# Buck.net
KiCad netlist of a schematic drawn in Altium Designer
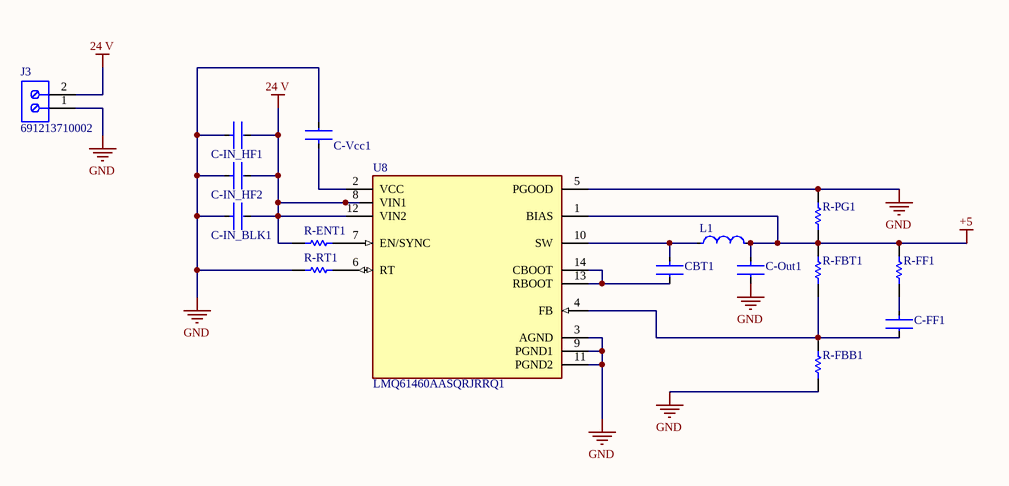
[diagram p0: Buck.SchDoc]

(export (version "E")
  (design (tool "Eeschema 10.0.6"))
  (components
    (comp (ref "C-FF1")
      (value "GRM188R60J106ME47D")
      (footprint "FP-GRM188-0_1-e0_2_0_55-IPC_A")
      (description "Chip Multilayer Ceramic Capacitors for General Purpose, 0603, 10uF, X5R, 15%, 20%, 6.3V")
      (fields (field (name "VOLTAGE") "6.3V") (field (name "TOLERANCE") "20%"))
      (libsource (lib "Altium Content Vault") (part "02cd4be3c70576c341d710602a673aa"))
    )
    (comp (ref "C-IN_BLK1")
      (value "GRM188R60J106ME47D")
      (footprint "FP-GRM188-0_1-e0_2_0_55-IPC_A")
      (description "Chip Multilayer Ceramic Capacitors for General Purpose, 0603, 10uF, X5R, 15%, 20%, 6.3V")
      (fields (field (name "VOLTAGE") "6.3V") (field (name "TOLERANCE") "20%"))
      (libsource (lib "Altium Content Vault") (part "02cd4be3c70576c341d710602a673aa"))
    )
    (comp (ref "C-IN_HF1")
      (value "GRM188R60J106ME47D")
      (footprint "FP-GRM188-0_1-e0_2_0_55-IPC_A")
      (description "Chip Multilayer Ceramic Capacitors for General Purpose, 0603, 10uF, X5R, 15%, 20%, 6.3V")
      (fields (field (name "VOLTAGE") "6.3V") (field (name "TOLERANCE") "20%"))
      (libsource (lib "Altium Content Vault") (part "02cd4be3c70576c341d710602a673aa"))
    )
    (comp (ref "C-IN_HF2")
      (value "GRM188R60J106ME47D")
      (footprint "FP-GRM188-0_1-e0_2_0_55-IPC_A")
      (description "Chip Multilayer Ceramic Capacitors for General Purpose, 0603, 10uF, X5R, 15%, 20%, 6.3V")
      (fields (field (name "VOLTAGE") "6.3V") (field (name "TOLERANCE") "20%"))
      (libsource (lib "Altium Content Vault") (part "02cd4be3c70576c341d710602a673aa"))
    )
    (comp (ref "C-Out1")
      (value "GRM188R60J106ME47D")
      (footprint "FP-GRM188-0_1-e0_2_0_55-IPC_A")
      (description "Chip Multilayer Ceramic Capacitors for General Purpose, 0603, 10uF, X5R, 15%, 20%, 6.3V")
      (fields (field (name "VOLTAGE") "6.3V") (field (name "TOLERANCE") "20%"))
      (libsource (lib "Altium Content Vault") (part "02cd4be3c70576c341d710602a673aa"))
    )
    (comp (ref "C-Vcc1")
      (value "GRM188R60J106ME47D")
      (footprint "FP-GRM188-0_1-e0_2_0_55-IPC_A")
      (description "Chip Multilayer Ceramic Capacitors for General Purpose, 0603, 10uF, X5R, 15%, 20%, 6.3V")
      (fields (field (name "VOLTAGE") "6.3V") (field (name "TOLERANCE") "20%"))
      (libsource (lib "Altium Content Vault") (part "02cd4be3c70576c341d710602a673aa"))
    )
    (comp (ref "CBT1")
      (value "GRM188R60J106ME47D")
      (footprint "FP-GRM188-0_1-e0_2_0_55-IPC_A")
      (description "Chip Multilayer Ceramic Capacitors for General Purpose, 0603, 10uF, X5R, 15%, 20%, 6.3V")
      (fields (field (name "VOLTAGE") "6.3V") (field (name "TOLERANCE") "20%"))
      (libsource (lib "Altium Content Vault") (part "02cd4be3c70576c341d710602a673aa"))
    )
    (comp (ref "J3")
      (value "691213710002")
      (footprint "691213710002")
      (fields (field (name "VOLTAGE") "300V"))
      (libsource (lib "Altium Content Vault") (part "TBL - 1R - 02P - Screw"))
    )
    (comp (ref "L1")
      (value "~")
      (footprint "FP-B82422A-MFG")
      (description "FIXED IND 10UH 180MA 1.6 OHM SMD")
      (fields (field (name "TOLERANCE") "10%"))
      (libsource (lib "Altium Content Vault") (part "725321dda6339637d4d059423bc1c3c"))
    )
    (comp (ref "R-ENT1")
      (value "~")
      (footprint "RESC1609X50X30NL8T20")
      (description "Chip Resistor, 0 Ohm, Jumper, 100 mW, -55 to 155 degC, 0603 (1608 Metric), RoHS, Tape and Reel")
      (fields (field (name "MANUFACTURER") "Vishay Semiconductor"))
      (libsource (lib "Altium Content Vault") (part "RES-2"))
    )
    (comp (ref "R-FBB1")
      (value "~")
      (footprint "RESC1609X50X30NL8T20")
      (description "Chip Resistor, 0 Ohm, Jumper, 100 mW, -55 to 155 degC, 0603 (1608 Metric), RoHS, Tape and Reel")
      (fields (field (name "MANUFACTURER") "Vishay Semiconductor"))
      (libsource (lib "Altium Content Vault") (part "RES-2"))
    )
    (comp (ref "R-FBT1")
      (value "~")
      (footprint "RESC1609X50X30NL8T20")
      (description "Chip Resistor, 0 Ohm, Jumper, 100 mW, -55 to 155 degC, 0603 (1608 Metric), RoHS, Tape and Reel")
      (fields (field (name "MANUFACTURER") "Vishay Semiconductor"))
      (libsource (lib "Altium Content Vault") (part "RES-2"))
    )
    (comp (ref "R-FF1")
      (value "~")
      (footprint "RESC1609X50X30NL8T20")
      (description "Chip Resistor, 0 Ohm, Jumper, 100 mW, -55 to 155 degC, 0603 (1608 Metric), RoHS, Tape and Reel")
      (fields (field (name "MANUFACTURER") "Vishay Semiconductor"))
      (libsource (lib "Altium Content Vault") (part "RES-2"))
    )
    (comp (ref "R-PG1")
      (value "~")
      (footprint "RESC1609X50X30NL8T20")
      (description "Chip Resistor, 0 Ohm, Jumper, 100 mW, -55 to 155 degC, 0603 (1608 Metric), RoHS, Tape and Reel")
      (fields (field (name "MANUFACTURER") "Vishay Semiconductor"))
      (libsource (lib "Altium Content Vault") (part "RES-2"))
    )
    (comp (ref "R-RT1")
      (value "~")
      (footprint "RESC1609X50X30NL8T20")
      (description "Chip Resistor, 0 Ohm, Jumper, 100 mW, -55 to 155 degC, 0603 (1608 Metric), RoHS, Tape and Reel")
      (fields (field (name "MANUFACTURER") "Vishay Semiconductor"))
      (libsource (lib "Altium Content Vault") (part "RES-2"))
    )
    (comp (ref "U8")
      (value "LMQ61460AASQRJRRQ1")
      (footprint "FP-RJR0014A-MFG")
      (description "AUTOMOTIVE 3-V TO 36-V, 6-A LOW")
      (libsource (lib "Altium Content Vault") (part "582341cdab2d02ffbfc5ca31c7a38c5"))
    )
  )
  (nets
    (net (code "1") (name "+5") (class "Default")
      (node (ref "C-Out1") (pin "1") (pinfunction "1_1") (pintype "passive"))
      (node (ref "L1") (pin "2") (pinfunction "2_2") (pintype "passive"))
      (node (ref "R-FBT1") (pin "2") (pinfunction "2_2") (pintype "passive"))
      (node (ref "R-FF1") (pin "2") (pinfunction "2_2") (pintype "passive"))
      (node (ref "R-PG1") (pin "1") (pinfunction "1_1") (pintype "passive"))
      (node (ref "U8") (pin "1") (pinfunction "BIAS_1") (pintype "passive"))
    )
    (net (code "2") (name "24 V") (class "Default")
      (node (ref "C-IN_BLK1") (pin "2") (pinfunction "2_2") (pintype "passive"))
      (node (ref "C-IN_HF1") (pin "2") (pinfunction "2_2") (pintype "passive"))
      (node (ref "C-IN_HF2") (pin "2") (pinfunction "2_2") (pintype "passive"))
      (node (ref "J3") (pin "2") (pinfunction "2_2") (pintype "passive"))
      (node (ref "R-ENT1") (pin "1") (pinfunction "1_1") (pintype "passive"))
      (node (ref "U8") (pin "12") (pinfunction "VIN2_12") (pintype "power_in"))
      (node (ref "U8") (pin "8") (pinfunction "VIN1_8") (pintype "power_in"))
    )
    (net (code "3") (name "GND") (class "Default")
      (node (ref "C-IN_BLK1") (pin "1") (pinfunction "1_1") (pintype "passive"))
      (node (ref "C-IN_HF1") (pin "1") (pinfunction "1_1") (pintype "passive"))
      (node (ref "C-IN_HF2") (pin "1") (pinfunction "1_1") (pintype "passive"))
      (node (ref "C-Out1") (pin "2") (pinfunction "2_2") (pintype "passive"))
      (node (ref "C-Vcc1") (pin "2") (pinfunction "2_2") (pintype "passive"))
      (node (ref "J3") (pin "1") (pinfunction "1_1") (pintype "passive"))
      (node (ref "R-FBB1") (pin "1") (pinfunction "1_1") (pintype "passive"))
      (node (ref "R-PG1") (pin "2") (pinfunction "2_2") (pintype "passive"))
      (node (ref "R-RT1") (pin "1") (pinfunction "1_1") (pintype "passive"))
      (node (ref "U8") (pin "11") (pinfunction "PGND2_11") (pintype "power_in"))
      (node (ref "U8") (pin "3") (pinfunction "AGND_3") (pintype "power_in"))
      (node (ref "U8") (pin "5") (pinfunction "PGOOD_5") (pintype "open_collector"))
      (node (ref "U8") (pin "9") (pinfunction "PGND1_9") (pintype "power_in"))
    )
    (net (code "4") (name "Net-(C-FF1-Pad1)") (class "Default")
      (node (ref "C-FF1") (pin "1") (pinfunction "1_1") (pintype "passive"))
      (node (ref "R-FF1") (pin "1") (pinfunction "1_1") (pintype "passive"))
    )
    (net (code "5") (name "Net-(U8-CBOOT)") (class "Default")
      (node (ref "CBT1") (pin "2") (pinfunction "2_2") (pintype "passive"))
      (node (ref "U8") (pin "13") (pinfunction "RBOOT_13") (pintype "passive"))
      (node (ref "U8") (pin "14") (pinfunction "CBOOT_14") (pintype "passive"))
    )
    (net (code "6") (name "Net-(U8-EN{slash}SYNC)") (class "Default")
      (node (ref "R-ENT1") (pin "2") (pinfunction "2_2") (pintype "passive"))
      (node (ref "U8") (pin "7") (pinfunction "EN/SYNC_7") (pintype "input"))
    )
    (net (code "7") (name "Net-(U8-FB)") (class "Default")
      (node (ref "C-FF1") (pin "2") (pinfunction "2_2") (pintype "passive"))
      (node (ref "R-FBB1") (pin "2") (pinfunction "2_2") (pintype "passive"))
      (node (ref "R-FBT1") (pin "1") (pinfunction "1_1") (pintype "passive"))
      (node (ref "U8") (pin "4") (pinfunction "FB_4") (pintype "input"))
    )
    (net (code "8") (name "Net-(U8-RT)") (class "Default")
      (node (ref "R-RT1") (pin "2") (pinfunction "2_2") (pintype "passive"))
      (node (ref "U8") (pin "6") (pinfunction "RT_6") (pintype "bidirectional"))
    )
    (net (code "9") (name "Net-(U8-SW)") (class "Default")
      (node (ref "CBT1") (pin "1") (pinfunction "1_1") (pintype "passive"))
      (node (ref "L1") (pin "1") (pinfunction "1_1") (pintype "passive"))
      (node (ref "U8") (pin "10") (pinfunction "SW_10") (pintype "passive"))
    )
    (net (code "10") (name "Net-(U8-VCC)") (class "Default")
      (node (ref "C-Vcc1") (pin "1") (pinfunction "1_1") (pintype "passive"))
      (node (ref "U8") (pin "2") (pinfunction "VCC_2") (pintype "power_in"))
    )
  )
)
